# MCU.net
KiCad netlist of a schematic drawn in Altium Designer
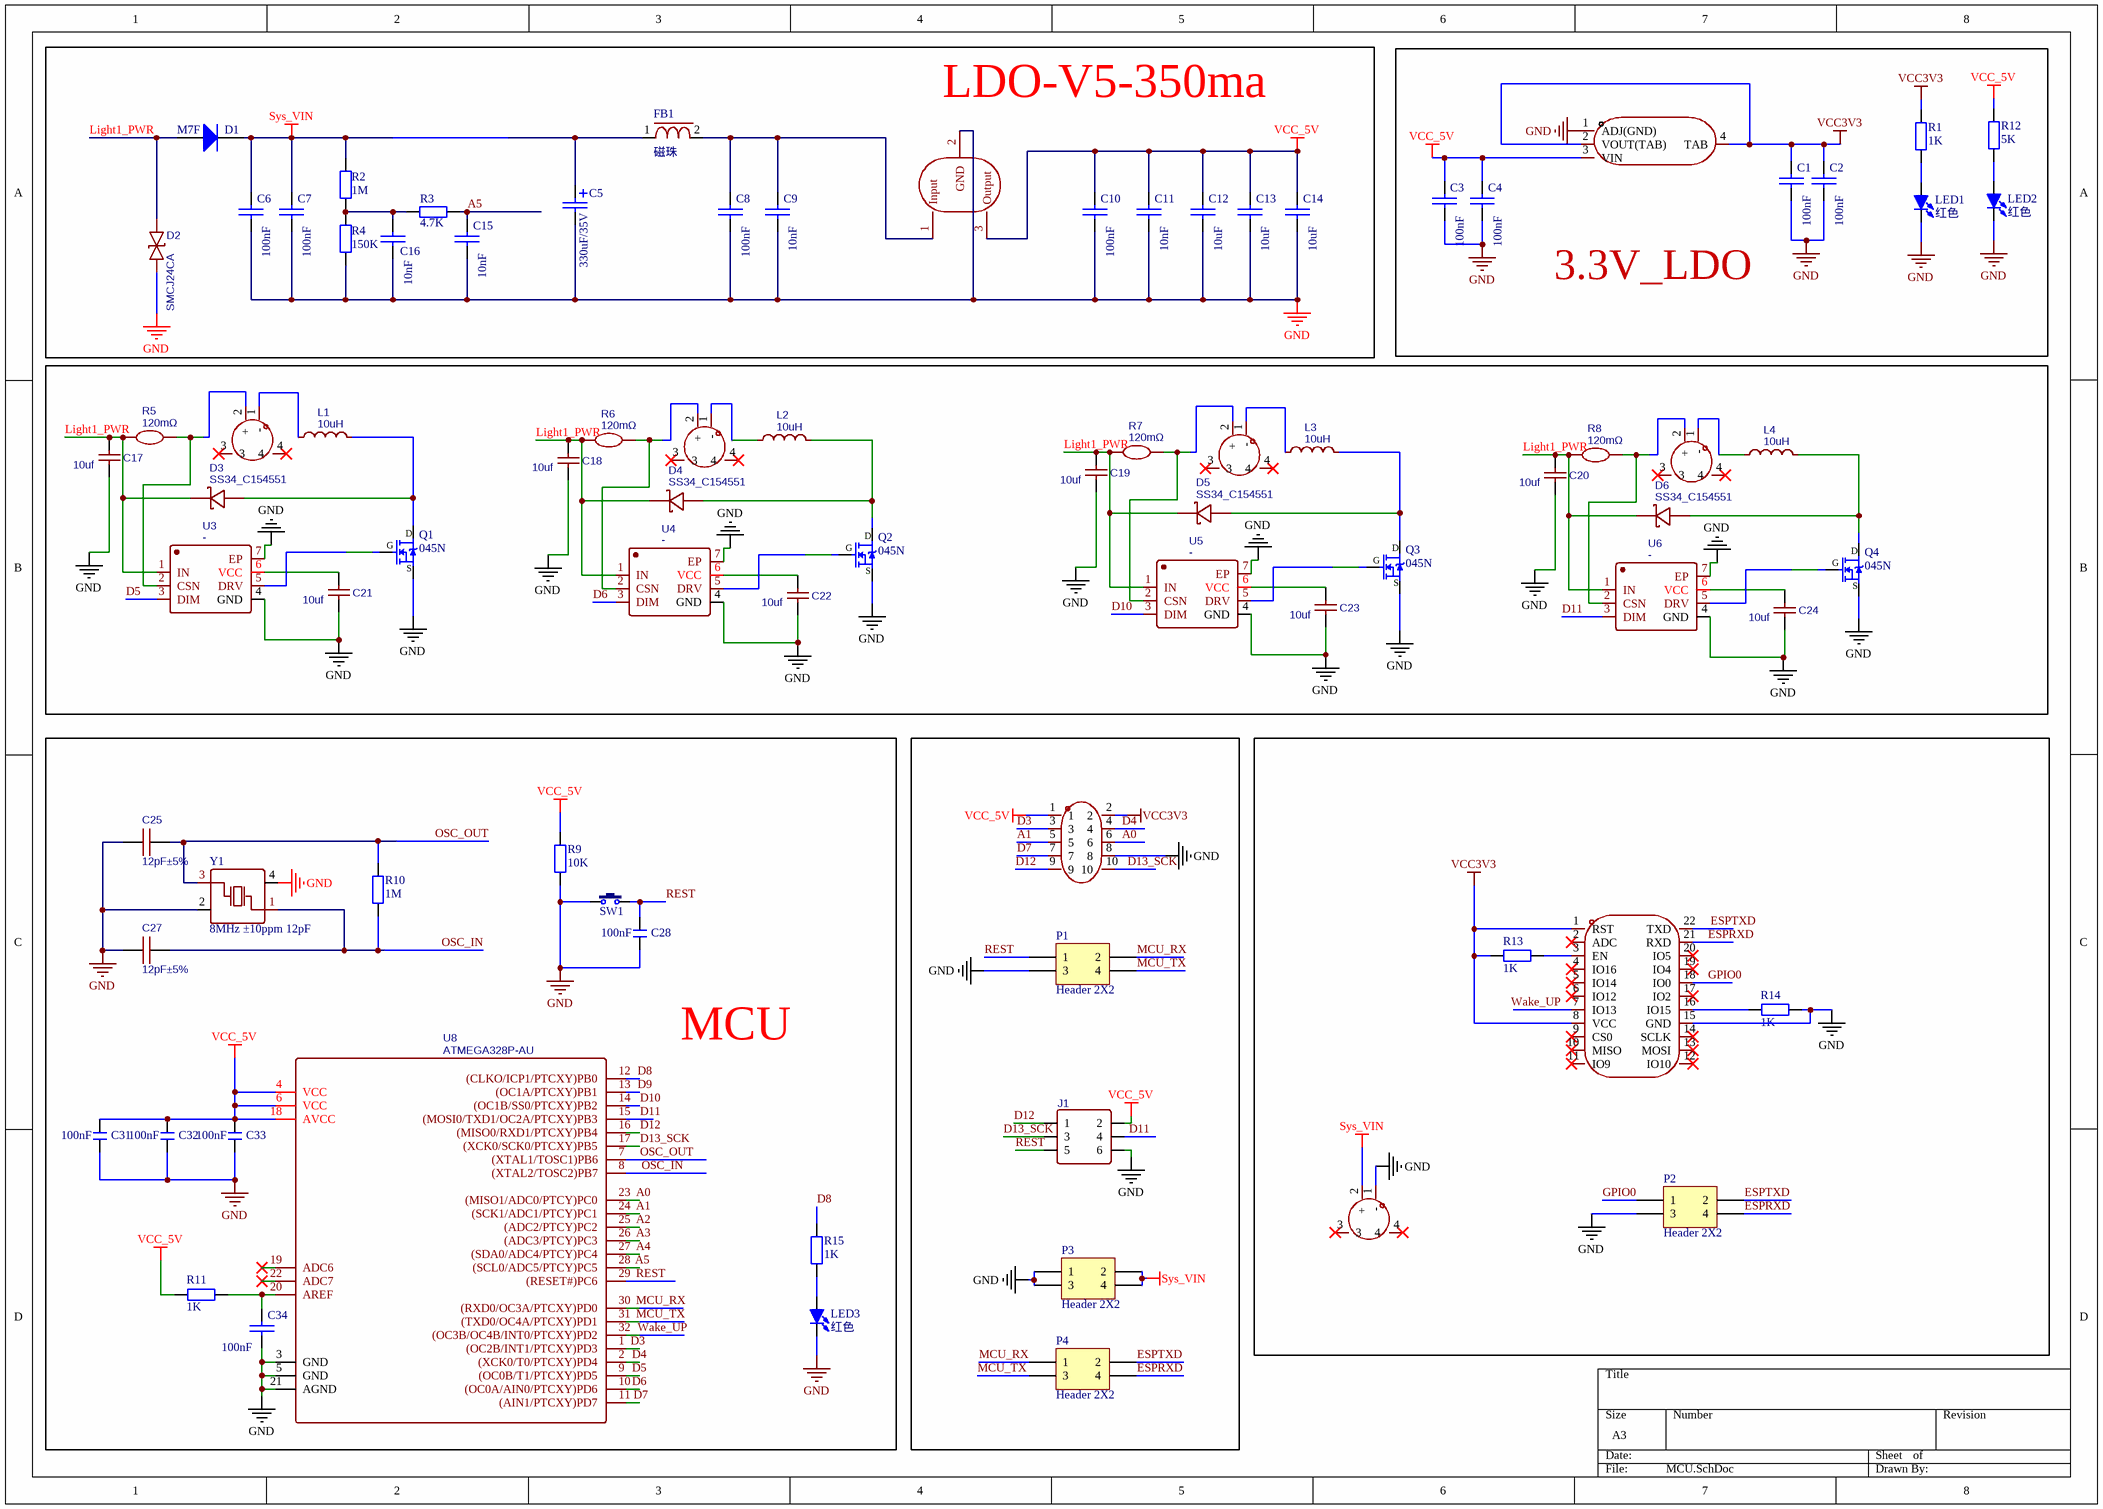
[diagram p0: MCU.SchDoc]

(export (version "E")
  (design (tool "Eeschema 10.0.6"))
  (components
    (comp (ref "C1")
      (value "100nF")
      (footprint "C_0603")
      (description "C_")
      (libsource (lib "MySchlib") (part "C_"))
    )
    (comp (ref "C2")
      (value "100nF")
      (footprint "C_0603")
      (description "C_")
      (libsource (lib "MySchlib") (part "C_"))
    )
    (comp (ref "C3")
      (value "100nF")
      (footprint "C_0603")
      (description "C_")
      (libsource (lib "MySchlib") (part "C_"))
    )
    (comp (ref "C4")
      (value "100nF")
      (footprint "C_0603")
      (description "C_")
      (libsource (lib "MySchlib") (part "C_"))
    )
    (comp (ref "C5")
      (value "330uF/35V")
      (footprint "9*H11MM")
      (description "RV331M035G105ETR，贴片电解，330u/35V/±20%/10X10.5")
      (libsource (lib "MySchlib") (part "C_ELEC_330uF,35V,10.0x10.5,CAPXON"))
    )
    (comp (ref "C6")
      (value "100nF")
      (footprint "C_0603")
      (description "C_")
      (libsource (lib "MySchlib") (part "C_"))
    )
    (comp (ref "C7")
      (value "100nF")
      (footprint "C_0603")
      (description "C_")
      (libsource (lib "MySchlib") (part "C_"))
    )
    (comp (ref "C8")
      (value "100nF")
      (footprint "C_0603")
      (description "C_")
      (libsource (lib "MySchlib") (part "C_"))
    )
    (comp (ref "C9")
      (value "10nF")
      (footprint "C_0603")
      (description "C_")
      (libsource (lib "MySchlib") (part "C_"))
    )
    (comp (ref "C10")
      (value "100nF")
      (footprint "C_0603")
      (description "C_")
      (libsource (lib "MySchlib") (part "C_"))
    )
    (comp (ref "C11")
      (value "10nF")
      (footprint "C_0603")
      (description "C_")
      (libsource (lib "MySchlib") (part "C_"))
    )
    (comp (ref "C12")
      (value "10uF")
      (footprint "C_1206")
      (description "C_")
      (libsource (lib "MySchlib") (part "C_"))
    )
    (comp (ref "C13")
      (value "10uF")
      (footprint "C_1206")
      (description "C_")
      (libsource (lib "MySchlib") (part "C_"))
    )
    (comp (ref "C14")
      (value "10uF")
      (footprint "C_1206")
      (description "C_")
      (libsource (lib "MySchlib") (part "C_"))
    )
    (comp (ref "C15")
      (value "10nF")
      (footprint "C_0603")
      (description "C_")
      (libsource (lib "MySchlib") (part "C_"))
    )
    (comp (ref "C16")
      (value "10nF")
      (footprint "C_0603")
      (description "C_")
      (libsource (lib "MySchlib") (part "C_"))
    )
    (comp (ref "C17")
      (value "10uf")
      (footprint "C_0603")
      (fields
        (field (name "MANUFACTURER") "muRata(村田)")
        (field (name "MANUFACTURER PART") "GCM188R70J225KE22D")
      )
      (libsource (lib "altium-import") (part "root_1_10uf_"))
    )
    (comp (ref "C18")
      (value "10uf")
      (footprint "C_0603")
      (fields
        (field (name "MANUFACTURER") "muRata(村田)")
        (field (name "MANUFACTURER PART") "GCM188R70J225KE22D")
      )
      (libsource (lib "altium-import") (part "root_1_10uf_"))
    )
    (comp (ref "C19")
      (value "10uf")
      (footprint "C_0603")
      (fields
        (field (name "MANUFACTURER") "muRata(村田)")
        (field (name "MANUFACTURER PART") "GCM188R70J225KE22D")
      )
      (libsource (lib "altium-import") (part "root_1_10uf_"))
    )
    (comp (ref "C20")
      (value "10uf")
      (footprint "C_0603")
      (fields
        (field (name "MANUFACTURER") "muRata(村田)")
        (field (name "MANUFACTURER PART") "GCM188R70J225KE22D")
      )
      (libsource (lib "altium-import") (part "root_1_10uf_"))
    )
    (comp (ref "C21")
      (value "10uf")
      (footprint "C_0603")
      (fields
        (field (name "MANUFACTURER") "muRata(村田)")
        (field (name "MANUFACTURER PART") "GCM188R70J225KE22D")
      )
      (libsource (lib "altium-import") (part "root_1_10uf_"))
    )
    (comp (ref "C22")
      (value "10uf")
      (footprint "C_0603")
      (fields
        (field (name "MANUFACTURER") "muRata(村田)")
        (field (name "MANUFACTURER PART") "GCM188R70J225KE22D")
      )
      (libsource (lib "altium-import") (part "root_1_10uf_"))
    )
    (comp (ref "C23")
      (value "10uf")
      (footprint "C_0603")
      (fields
        (field (name "MANUFACTURER") "muRata(村田)")
        (field (name "MANUFACTURER PART") "GCM188R70J225KE22D")
      )
      (libsource (lib "altium-import") (part "root_1_10uf_"))
    )
    (comp (ref "C24")
      (value "10uf")
      (footprint "C_0603")
      (fields
        (field (name "MANUFACTURER") "muRata(村田)")
        (field (name "MANUFACTURER PART") "GCM188R70J225KE22D")
      )
      (libsource (lib "altium-import") (part "root_1_10uf_"))
    )
    (comp (ref "C25")
      (value "12pF±5%")
      (footprint "C_0603")
      (description "电容")
      (libsource (lib "项目常用") (part "CAP"))
    )
    (comp (ref "C27")
      (value "12pF±5%")
      (footprint "C_0603")
      (description "电容")
      (libsource (lib "项目常用") (part "CAP"))
    )
    (comp (ref "C28")
      (value "100nF")
      (footprint "C_0603")
      (description "无极性贴片电容")
      (fields (field (name "版权归属") "源创客"))
      (libsource (lib "BULETOOTH") (part "C"))
    )
    (comp (ref "C31")
      (value "100nF")
      (footprint "C_0603")
      (description "无极性贴片电容")
      (fields (field (name "版权归属") "源创客"))
      (libsource (lib "BULETOOTH") (part "C"))
    )
    (comp (ref "C32")
      (value "100nF")
      (footprint "C_0603")
      (description "无极性贴片电容")
      (fields (field (name "版权归属") "源创客"))
      (libsource (lib "BULETOOTH") (part "C"))
    )
    (comp (ref "C33")
      (value "100nF")
      (footprint "C_0603")
      (description "无极性贴片电容")
      (fields (field (name "版权归属") "源创客"))
      (libsource (lib "BULETOOTH") (part "C"))
    )
    (comp (ref "C34")
      (value "100nF")
      (footprint "C_0603")
      (description "C_")
      (libsource (lib "MySchlib") (part "C_"))
    )
    (comp (ref "CN1")
      (value "XT60PW-M")
      (footprint "CONN-TH_XT60PW-M - duplicate")
      (fields (field (name "MANUFACTURER") "AMASS(艾迈斯)"))
      (libsource (lib "altium-import") (part "root_3_XT60PW-M_"))
    )
    (comp (ref "CN2")
      (value "XT60PW-M")
      (footprint "CONN-TH_XT60PW-M - duplicate")
      (fields (field (name "MANUFACTURER") "AMASS(艾迈斯)"))
      (libsource (lib "altium-import") (part "root_3_XT60PW-M_"))
    )
    (comp (ref "CN3")
      (value "XT60PW-M")
      (footprint "CONN-TH_XT60PW-M - duplicate")
      (fields (field (name "MANUFACTURER") "AMASS(艾迈斯)"))
      (libsource (lib "altium-import") (part "root_3_XT60PW-M_"))
    )
    (comp (ref "CN4")
      (value "XT60PW-M")
      (footprint "CONN-TH_XT60PW-M - duplicate")
      (fields (field (name "MANUFACTURER") "AMASS(艾迈斯)"))
      (libsource (lib "altium-import") (part "root_3_XT60PW-M_"))
    )
    (comp (ref "CN5")
      (value "JL15EDGRHC-35005B02")
      (footprint "CONN-TH_5P-P3.50_JILN_JL15EDGRHC-35005B02")
      (fields (field (name "MANUFACTURER") "JILN(锦凌)"))
      (libsource (lib "altium-import") (part "root_0_JL15EDGRHC-35005B02_"))
    )
    (comp (ref "CN6")
      (value "XT60PW-M")
      (footprint "CONN-TH_XT60PW-M - duplicate")
      (fields (field (name "MANUFACTURER") "AMASS(艾迈斯)"))
      (libsource (lib "altium-import") (part "root_3_XT60PW-M_"))
    )
    (comp (ref "D1")
      (value "M7F")
      (footprint "SMA")
      (description "M7F,二极管/1000V/1A/1.1V/SMAF/-55oC~150oC")
      (libsource (lib "MySchlib") (part "D_M7F,SMAF,MCC"))
    )
    (comp (ref "D2")
      (value "SMCJ24CA")
      (footprint "SMC")
      (fields
        (field (name "BOM_SUPPLIER PART") "C169449")
        (field (name "BOM_MANUFACTURER PART") "SMBJ15CA")
        (field (name "CONTRIBUTOR") "LCSC")
      )
      (libsource (lib "项目常用") (part "SMBJ15CA"))
    )
    (comp (ref "D3")
      (value "SS34_C154551")
      (footprint "SMC")
      (fields
        (field (name "MANUFACTURER") "onsemi(安森美)")
        (field (name "MANUFACTURER PART") "SS34")
        (field (name "CONTRIBUTOR") "LCSC")
      )
      (libsource (lib "altium-import") (part "root_0_SS34_C154551_"))
    )
    (comp (ref "D4")
      (value "SS34_C154551")
      (footprint "SMC")
      (fields
        (field (name "MANUFACTURER") "onsemi(安森美)")
        (field (name "MANUFACTURER PART") "SS34")
        (field (name "CONTRIBUTOR") "LCSC")
      )
      (libsource (lib "altium-import") (part "root_0_SS34_C154551_"))
    )
    (comp (ref "D5")
      (value "SS34_C154551")
      (footprint "SMC")
      (fields
        (field (name "MANUFACTURER") "onsemi(安森美)")
        (field (name "MANUFACTURER PART") "SS34")
        (field (name "CONTRIBUTOR") "LCSC")
      )
      (libsource (lib "altium-import") (part "root_0_SS34_C154551_"))
    )
    (comp (ref "D6")
      (value "SS34_C154551")
      (footprint "SMC")
      (fields
        (field (name "MANUFACTURER") "onsemi(安森美)")
        (field (name "MANUFACTURER PART") "SS34")
        (field (name "CONTRIBUTOR") "LCSC")
      )
      (libsource (lib "altium-import") (part "root_0_SS34_C154551_"))
    )
    (comp (ref "FB1")
      (value "磁珠")
      (footprint "R_0805")
      (description "UPB201209T-101Y-N,磁珠/100Ω/5A/0805,奇力新")
      (libsource (lib "项目常用") (part "磁珠"))
    )
    (comp (ref "J1")
      (value "HDR-M-2.54_2x3")
      (footprint "HDR-3X2")
      (fields (field (name "BOM_SUPPLIER PART") "C65114") (field (name "CONTRIBUTOR") "LCEDA_Lib"))
      (libsource (lib "altium-import") (part "root_0_HDR-M-2.54_2x3_"))
    )
    (comp (ref "L1")
      (value "10uH")
      (footprint "IND-SMD_L7.0-W6.6_FXL0650")
      (fields
        (field (name "MANUFACTURER") "cjiang(长江微电)")
        (field (name "MANUFACTURER PART") "FXL0650-8R2-M")
        (field (name "CONTRIBUTOR") "LCSC")
      )
      (libsource (lib "altium-import") (part "root_0_10uH_"))
    )
    (comp (ref "L2")
      (value "10uH")
      (footprint "IND-SMD_L7.0-W6.6_FXL0650")
      (fields
        (field (name "MANUFACTURER") "cjiang(长江微电)")
        (field (name "MANUFACTURER PART") "FXL0650-8R2-M")
        (field (name "CONTRIBUTOR") "LCSC")
      )
      (libsource (lib "altium-import") (part "root_0_10uH_"))
    )
    (comp (ref "L3")
      (value "10uH")
      (footprint "IND-SMD_L7.0-W6.6_FXL0650")
      (fields
        (field (name "MANUFACTURER") "cjiang(长江微电)")
        (field (name "MANUFACTURER PART") "FXL0650-8R2-M")
        (field (name "CONTRIBUTOR") "LCSC")
      )
      (libsource (lib "altium-import") (part "root_0_10uH_"))
    )
    (comp (ref "L4")
      (value "10uH")
      (footprint "IND-SMD_L7.0-W6.6_FXL0650")
      (fields
        (field (name "MANUFACTURER") "cjiang(长江微电)")
        (field (name "MANUFACTURER PART") "FXL0650-8R2-M")
        (field (name "CONTRIBUTOR") "LCSC")
      )
      (libsource (lib "altium-import") (part "root_0_10uH_"))
    )
    (comp (ref "LED1")
      (value "红色")
      (footprint "LED 0805G")
      (description "贴片LED")
      (fields (field (name "版权归属") "源创客"))
      (libsource (lib "LED") (part "LED-SMD"))
    )
    (comp (ref "LED2")
      (value "红色")
      (footprint "LED 0805G")
      (description "贴片LED")
      (fields (field (name "版权归属") "源创客"))
      (libsource (lib "LED") (part "LED-SMD"))
    )
    (comp (ref "LED3")
      (value "红色")
      (footprint "LED 0805G")
      (description "贴片LED")
      (fields (field (name "版权归属") "源创客"))
      (libsource (lib "LED") (part "LED-SMD"))
    )
    (comp (ref "P1")
      (value "Header 2X2")
      (footprint "HDR-2X2")
      (description "Header, 2-Pin, Dual row")
      (fields (field (name "PUBLISHER") "Altium Limited"))
      (libsource (lib "Miscellaneous Connectors") (part "Header 2X2"))
    )
    (comp (ref "P2")
      (value "Header 2X2")
      (footprint "HDR-2X2")
      (description "Header, 2-Pin, Dual row")
      (fields (field (name "PUBLISHER") "Altium Limited"))
      (libsource (lib "Miscellaneous Connectors") (part "Header 2X2"))
    )
    (comp (ref "P3")
      (value "Header 2X2")
      (footprint "HDR-2X2")
      (description "Header, 2-Pin, Dual row")
      (fields (field (name "PUBLISHER") "Altium Limited"))
      (libsource (lib "Miscellaneous Connectors") (part "Header 2X2"))
    )
    (comp (ref "P4")
      (value "Header 2X2")
      (footprint "HDR-2X2")
      (description "Header, 2-Pin, Dual row")
      (fields (field (name "PUBLISHER") "Altium Limited"))
      (libsource (lib "Miscellaneous Connectors") (part "Header 2X2"))
    )
    (comp (ref "Q1")
      (value "045N")
      (footprint "TDSON-8_L5.9-W5.2-P1.27-BL")
      (description "CRSM045N04N2Z")
      (fields (field (name "版权归属") "源创客"))
      (libsource (lib "6.1   - 场效应管-可控硅") (part "10N65"))
    )
    (comp (ref "Q2")
      (value "045N")
      (footprint "TDSON-8_L5.9-W5.2-P1.27-BL")
      (description "CRSM045N04N2Z")
      (fields (field (name "版权归属") "源创客"))
      (libsource (lib "6.1   - 场效应管-可控硅") (part "10N65"))
    )
    (comp (ref "Q3")
      (value "045N")
      (footprint "TDSON-8_L5.9-W5.2-P1.27-BL")
      (description "CRSM045N04N2Z")
      (fields (field (name "版权归属") "源创客"))
      (libsource (lib "6.1   - 场效应管-可控硅") (part "10N65"))
    )
    (comp (ref "Q4")
      (value "045N")
      (footprint "TDSON-8_L5.9-W5.2-P1.27-BL")
      (description "CRSM045N04N2Z")
      (fields (field (name "版权归属") "源创客"))
      (libsource (lib "6.1   - 场效应管-可控硅") (part "10N65"))
    )
    (comp (ref "R1")
      (value "1K")
      (footprint "R_0603")
      (description "大功率电阻")
      (fields (field (name "版权归属") "源创客"))
      (libsource (lib "3.1   - 电阻-电容-电感") (part "RX"))
    )
    (comp (ref "R2")
      (value "1M")
      (footprint "R_0603")
      (description "贴片电阻")
      (libsource (lib "MySchlib") (part "R_"))
    )
    (comp (ref "R3")
      (value "4.7K")
      (footprint "R_0603")
      (description "贴片电阻")
      (libsource (lib "") (part "R__1"))
    )
    (comp (ref "R4")
      (value "150K")
      (footprint "R_0603")
      (description "贴片电阻")
      (libsource (lib "MySchlib") (part "R_"))
    )
    (comp (ref "R5")
      (value "120mΩ")
      (footprint "R 2512-HP")
      (fields
        (field (name "MANUFACTURER") "Milliohm(毫欧)")
        (field (name "MANUFACTURER PART") "HoJLR2512-3W-120mR-1%")
        (field (name "CONTRIBUTOR") "lcsc")
      )
      (libsource (lib "altium-import") (part "root_0_120mΩ_"))
    )
    (comp (ref "R6")
      (value "120mΩ")
      (footprint "R 2512-HP")
      (fields
        (field (name "MANUFACTURER") "Milliohm(毫欧)")
        (field (name "MANUFACTURER PART") "HoJLR2512-3W-120mR-1%")
        (field (name "CONTRIBUTOR") "lcsc")
      )
      (libsource (lib "altium-import") (part "root_0_120mΩ_"))
    )
    (comp (ref "R7")
      (value "120mΩ")
      (footprint "R 2512-HP")
      (fields
        (field (name "MANUFACTURER") "Milliohm(毫欧)")
        (field (name "MANUFACTURER PART") "HoJLR2512-3W-120mR-1%")
        (field (name "CONTRIBUTOR") "lcsc")
      )
      (libsource (lib "altium-import") (part "root_0_120mΩ_"))
    )
    (comp (ref "R8")
      (value "120mΩ")
      (footprint "R 2512-HP")
      (fields
        (field (name "MANUFACTURER") "Milliohm(毫欧)")
        (field (name "MANUFACTURER PART") "HoJLR2512-3W-120mR-1%")
        (field (name "CONTRIBUTOR") "lcsc")
      )
      (libsource (lib "altium-import") (part "root_0_120mΩ_"))
    )
    (comp (ref "R9")
      (value "10K")
      (footprint "R_0603")
      (description "大功率电阻")
      (fields (field (name "版权归属") "源创客"))
      (libsource (lib "3.1   - 电阻-电容-电感") (part "RX"))
    )
    (comp (ref "R10")
      (value "1M")
      (footprint "R_0603")
      (description "大功率电阻")
      (fields (field (name "版权归属") "源创客"))
      (libsource (lib "3.1   - 电阻-电容-电感") (part "RX"))
    )
    (comp (ref "R11")
      (value "1K")
      (footprint "R_0603")
      (description "大功率电阻")
      (fields (field (name "版权归属") "源创客"))
      (libsource (lib "3.1   - 电阻-电容-电感") (part "RX"))
    )
    (comp (ref "R12")
      (value "5K")
      (footprint "R_0603")
      (description "大功率电阻")
      (fields (field (name "版权归属") "源创客"))
      (libsource (lib "3.1   - 电阻-电容-电感") (part "RX"))
    )
    (comp (ref "R13")
      (value "1K")
      (footprint "R_0603")
      (description "大功率电阻")
      (fields (field (name "版权归属") "源创客"))
      (libsource (lib "3.1   - 电阻-电容-电感") (part "RX"))
    )
    (comp (ref "R14")
      (value "1K")
      (footprint "R_0603")
      (description "大功率电阻")
      (fields (field (name "版权归属") "源创客"))
      (libsource (lib "3.1   - 电阻-电容-电感") (part "RX"))
    )
    (comp (ref "R15")
      (value "1K")
      (footprint "R_0603")
      (description "大功率电阻")
      (fields (field (name "版权归属") "源创客"))
      (libsource (lib "3.1   - 电阻-电容-电感") (part "RX"))
    )
    (comp (ref "SW1")
      (value "3x6x5")
      (footprint "TSW SMD-3*6*2.5")
      (description "3x6轻触开关")
      (fields (field (name "版权归属") "源创客"))
      (libsource (lib "按键-开关") (part "TSW 3x6"))
    )
    (comp (ref "U1")
      (value "AMS1117-3.3")
      (footprint "SOT223_L")
      (fields (field (name "MANUFACTURER") "UMW(友台半导体)"))
      (libsource (lib "altium-import") (part "root_0_AMS1117-3.3_C347222_"))
    )
    (comp (ref "U2")
      (value "DIA7875B50TA3")
      (footprint "SOT223_N")
      (libsource (lib "MySchlib") (part "DIA7875"))
    )
    (comp (ref "U3")
      (value "-")
      (footprint "TDFN-6_L3.0-W3.0-P0.95-BL-EP")
      (fields
        (field (name "MANUFACTURER") "ADI(亚德诺)/MAXIM(美信)")
        (field (name "MANUFACTURER PART") "MAX16819ATT+T")
        (field (name "CONTRIBUTOR") "LCSC")
      )
      (libsource (lib "altium-import") (part "root_0_-_"))
    )
    (comp (ref "U4")
      (value "-")
      (footprint "TDFN-6_L3.0-W3.0-P0.95-BL-EP")
      (fields
        (field (name "MANUFACTURER") "ADI(亚德诺)/MAXIM(美信)")
        (field (name "MANUFACTURER PART") "MAX16819ATT+T")
        (field (name "CONTRIBUTOR") "LCSC")
      )
      (libsource (lib "altium-import") (part "root_0_-_"))
    )
    (comp (ref "U5")
      (value "-")
      (footprint "TDFN-6_L3.0-W3.0-P0.95-BL-EP")
      (fields
        (field (name "MANUFACTURER") "ADI(亚德诺)/MAXIM(美信)")
        (field (name "MANUFACTURER PART") "MAX16819ATT+T")
        (field (name "CONTRIBUTOR") "LCSC")
      )
      (libsource (lib "altium-import") (part "root_0_-_"))
    )
    (comp (ref "U6")
      (value "-")
      (footprint "TDFN-6_L3.0-W3.0-P0.95-BL-EP")
      (fields
        (field (name "MANUFACTURER") "ADI(亚德诺)/MAXIM(美信)")
        (field (name "MANUFACTURER PART") "MAX16819ATT+T")
        (field (name "CONTRIBUTOR") "LCSC")
      )
      (libsource (lib "altium-import") (part "root_0_-_"))
    )
    (comp (ref "U7")
      (value "2.4GHz")
      (footprint "WIRELM-SMD_ESP-12F")
      (fields (field (name "MANUFACTURER") "DOIT(四博智联)") (field (name "MANUFACTURER PART") "ESP-12F"))
      (libsource (lib "altium-import") (part "root_0_ESP-12F_"))
    )
    (comp (ref "U8")
      (value "ATMEGA328P-AU")
      (footprint "TQFP-32_L7.0-W7.0-P0.80-LS9.0-BL")
      (fields (field (name "BOM_SUPPLIER PART") "C14877") (field (name "CONTRIBUTOR") "13471635540"))
      (libsource (lib "altium-import") (part "root_0_ATMEGA328P-AU_"))
    )
    (comp (ref "Y1")
      (value "8MHz ±10ppm 12pF")
      (footprint "SMD-3225-4P")
      (libsource (lib "项目常用") (part "晶振4P"))
    )
  )
  (nets
    (net (code "1") (name "/A0") (class "Default")
      (node (ref "CN5") (pin "6") (pinfunction "6_6") (pintype "passive"))
      (node (ref "U8") (pin "23") (pinfunction "(MISO1/ADC0/PTCY)PC0_23") (pintype "passive"))
    )
    (net (code "2") (name "/A1") (class "Default")
      (node (ref "CN5") (pin "5") (pinfunction "5_5") (pintype "passive"))
      (node (ref "U8") (pin "24") (pinfunction "(SCK1/ADC1/PTCY)PC1_24") (pintype "passive"))
    )
    (net (code "3") (name "/A2") (class "Default")
      (node (ref "U8") (pin "25") (pinfunction "(ADC2/PTCY)PC2_25") (pintype "passive"))
    )
    (net (code "4") (name "/A3") (class "Default")
      (node (ref "U8") (pin "26") (pinfunction "(ADC3/PTCY)PC3_26") (pintype "passive"))
    )
    (net (code "5") (name "/A4") (class "Default")
      (node (ref "U8") (pin "27") (pinfunction "(SDA0/ADC4/PTCY)PC4_27") (pintype "passive"))
    )
    (net (code "6") (name "/A5") (class "Default")
      (node (ref "C15") (pin "1") (pinfunction "1_1") (pintype "passive"))
      (node (ref "R3") (pin "1") (pinfunction "1_1") (pintype "passive"))
      (node (ref "U8") (pin "28") (pinfunction "(SCL0/ADC5/PTCY)PC5_28") (pintype "passive"))
    )
    (net (code "7") (name "/D3") (class "Default")
      (node (ref "CN5") (pin "3") (pinfunction "3_3") (pintype "passive"))
      (node (ref "U8") (pin "1") (pinfunction "(OC2B/INT1/PTCXY)PD3_1") (pintype "passive"))
    )
    (net (code "8") (name "/D4") (class "Default")
      (node (ref "CN5") (pin "4") (pinfunction "4_4") (pintype "passive"))
      (node (ref "U8") (pin "2") (pinfunction "(XCK0/T0/PTCXY)PD4_2") (pintype "passive"))
    )
    (net (code "9") (name "/D5") (class "Default")
      (node (ref "U3") (pin "3") (pinfunction "DIM_3") (pintype "passive"))
      (node (ref "U8") (pin "9") (pinfunction "(OC0B/T1/PTCXY)PD5_9") (pintype "passive"))
    )
    (net (code "10") (name "/D6") (class "Default")
      (node (ref "U4") (pin "3") (pinfunction "DIM_3") (pintype "passive"))
      (node (ref "U8") (pin "10") (pinfunction "(OC0A/AIN0/PTCXY)PD6_10") (pintype "passive"))
    )
    (net (code "11") (name "/D7") (class "Default")
      (node (ref "CN5") (pin "7") (pinfunction "7_7") (pintype "passive"))
      (node (ref "U8") (pin "11") (pinfunction "(AIN1/PTCXY)PD7_11") (pintype "passive"))
    )
    (net (code "12") (name "/D8") (class "Default")
      (node (ref "R15") (pin "2") (pinfunction "2_2") (pintype "passive"))
      (node (ref "U8") (pin "12") (pinfunction "(CLKO/ICP1/PTCXY)PB0_12") (pintype "passive"))
    )
    (net (code "13") (name "/D9") (class "Default")
      (node (ref "U8") (pin "13") (pinfunction "(OC1A/PTCXY)PB1_13") (pintype "passive"))
    )
    (net (code "14") (name "/D10") (class "Default")
      (node (ref "U5") (pin "3") (pinfunction "DIM_3") (pintype "passive"))
      (node (ref "U8") (pin "14") (pinfunction "(OC1B/SS0/PTCXY)PB2_14") (pintype "passive"))
    )
    (net (code "15") (name "/D11") (class "Default")
      (node (ref "J1") (pin "4") (pinfunction "4_4") (pintype "passive"))
      (node (ref "U6") (pin "3") (pinfunction "DIM_3") (pintype "passive"))
      (node (ref "U8") (pin "15") (pinfunction "(MOSI0/TXD1/OC2A/PTCXY)PB3_15") (pintype "passive"))
    )
    (net (code "16") (name "/D12") (class "Default")
      (node (ref "CN5") (pin "9") (pinfunction "9_9") (pintype "passive"))
      (node (ref "J1") (pin "1") (pinfunction "1_1") (pintype "passive"))
      (node (ref "U8") (pin "16") (pinfunction "(MISO0/RXD1/PTCXY)PB4_16") (pintype "passive"))
    )
    (net (code "17") (name "/D13_SCK") (class "Default")
      (node (ref "CN5") (pin "10") (pinfunction "10_10") (pintype "passive"))
      (node (ref "J1") (pin "3") (pinfunction "3_3") (pintype "passive"))
      (node (ref "U8") (pin "17") (pinfunction "(XCK0/SCK0/PTCXY)PB5_17") (pintype "passive"))
    )
    (net (code "18") (name "/ESPRXD") (class "Default")
      (node (ref "P2") (pin "4") (pinfunction "4_4") (pintype "passive"))
      (node (ref "P4") (pin "4") (pinfunction "4_4") (pintype "passive"))
      (node (ref "U7") (pin "21") (pinfunction "RXD_21") (pintype "passive"))
    )
    (net (code "19") (name "/ESPTXD") (class "Default")
      (node (ref "P2") (pin "2") (pinfunction "2_2") (pintype "passive"))
      (node (ref "P4") (pin "2") (pinfunction "2_2") (pintype "passive"))
      (node (ref "U7") (pin "22") (pinfunction "TXD_22") (pintype "passive"))
    )
    (net (code "20") (name "/GPIO0") (class "Default")
      (node (ref "P2") (pin "1") (pinfunction "1_1") (pintype "passive"))
      (node (ref "U7") (pin "18") (pinfunction "IO0_18") (pintype "passive"))
    )
    (net (code "21") (name "/Light1_PWR") (class "Default")
      (node (ref "C17") (pin "2") (pinfunction "2_2") (pintype "passive"))
      (node (ref "C18") (pin "2") (pinfunction "2_2") (pintype "passive"))
      (node (ref "C19") (pin "2") (pinfunction "2_2") (pintype "passive"))
      (node (ref "C20") (pin "2") (pinfunction "2_2") (pintype "passive"))
      (node (ref "D1") (pin "1") (pinfunction "A_1") (pintype "passive"))
      (node (ref "D2") (pin "1") (pinfunction "1_1") (pintype "passive"))
      (node (ref "D3") (pin "1") (pinfunction "C_1") (pintype "passive"))
      (node (ref "D4") (pin "1") (pinfunction "C_1") (pintype "passive"))
      (node (ref "D5") (pin "1") (pinfunction "C_1") (pintype "passive"))
      (node (ref "D6") (pin "1") (pinfunction "C_1") (pintype "passive"))
      (node (ref "R5") (pin "1") (pinfunction "1_1") (pintype "passive"))
      (node (ref "R6") (pin "1") (pinfunction "1_1") (pintype "passive"))
      (node (ref "R7") (pin "1") (pinfunction "1_1") (pintype "passive"))
      (node (ref "R8") (pin "1") (pinfunction "1_1") (pintype "passive"))
      (node (ref "U3") (pin "1") (pinfunction "IN_1") (pintype "passive"))
      (node (ref "U4") (pin "1") (pinfunction "IN_1") (pintype "passive"))
      (node (ref "U5") (pin "1") (pinfunction "IN_1") (pintype "passive"))
      (node (ref "U6") (pin "1") (pinfunction "IN_1") (pintype "passive"))
    )
    (net (code "22") (name "/MCU_RX") (class "Default")
      (node (ref "P1") (pin "2") (pinfunction "2_2") (pintype "passive"))
      (node (ref "P4") (pin "1") (pinfunction "1_1") (pintype "passive"))
      (node (ref "U8") (pin "30") (pinfunction "(RXD0/OC3A/PTCXY)PD0_30") (pintype "passive"))
    )
    (net (code "23") (name "/MCU_TX") (class "Default")
      (node (ref "P1") (pin "4") (pinfunction "4_4") (pintype "passive"))
      (node (ref "P4") (pin "3") (pinfunction "3_3") (pintype "passive"))
      (node (ref "U8") (pin "31") (pinfunction "(TXD0/OC4A/PTCXY)PD1_31") (pintype "passive"))
    )
    (net (code "24") (name "/OSC_IN") (class "Default")
      (node (ref "C27") (pin "2") (pinfunction "K_2") (pintype "passive"))
      (node (ref "R10") (pin "1") (pinfunction "1_1") (pintype "passive"))
      (node (ref "U8") (pin "8") (pinfunction "(XTAL2/TOSC2)PB7_8") (pintype "passive"))
      (node (ref "Y1") (pin "1") (pinfunction "OSC1_1") (pintype "passive"))
    )
    (net (code "25") (name "/OSC_OUT") (class "Default")
      (node (ref "C25") (pin "2") (pinfunction "K_2") (pintype "passive"))
      (node (ref "R10") (pin "2") (pinfunction "2_2") (pintype "passive"))
      (node (ref "U8") (pin "7") (pinfunction "(XTAL1/TOSC1)PB6_7") (pintype "passive"))
      (node (ref "Y1") (pin "3") (pinfunction "OSC2_3") (pintype "passive"))
    )
    (net (code "26") (name "/REST") (class "Default")
      (node (ref "C28") (pin "2") (pinfunction "2_2") (pintype "passive"))
      (node (ref "J1") (pin "5") (pinfunction "5_5") (pintype "passive"))
      (node (ref "P1") (pin "1") (pinfunction "1_1") (pintype "passive"))
      (node (ref "SW1") (pin "2") (pinfunction "2_2") (pintype "passive"))
      (node (ref "U8") (pin "29") (pinfunction "(RESET#)PC6_29") (pintype "passive"))
    )
    (net (code "27") (name "/Wake_UP") (class "Default")
      (node (ref "U8") (pin "32") (pinfunction "(OC3B/OC4B/INT0/PTCXY)PD2_32") (pintype "passive"))
    )
    (net (code "28") (name "GND") (class "Default")
      (node (ref "C1") (pin "2") (pinfunction "2_2") (pintype "passive"))
      (node (ref "C10") (pin "2") (pinfunction "2_2") (pintype "passive"))
      (node (ref "C11") (pin "2") (pinfunction "2_2") (pintype "passive"))
      (node (ref "C12") (pin "2") (pinfunction "2_2") (pintype "passive"))
      (node (ref "C13") (pin "2") (pinfunction "2_2") (pintype "passive"))
      (node (ref "C14") (pin "2") (pinfunction "2_2") (pintype "passive"))
      (node (ref "C15") (pin "2") (pinfunction "2_2") (pintype "passive"))
      (node (ref "C16") (pin "2") (pinfunction "2_2") (pintype "passive"))
      (node (ref "C17") (pin "1") (pinfunction "1_1") (pintype "passive"))
      (node (ref "C18") (pin "1") (pinfunction "1_1") (pintype "passive"))
      (node (ref "C19") (pin "1") (pinfunction "1_1") (pintype "passive"))
      (node (ref "C2") (pin "2") (pinfunction "2_2") (pintype "passive"))
      (node (ref "C20") (pin "1") (pinfunction "1_1") (pintype "passive"))
      (node (ref "C21") (pin "1") (pinfunction "1_1") (pintype "passive"))
      (node (ref "C22") (pin "1") (pinfunction "1_1") (pintype "passive"))
      (node (ref "C23") (pin "1") (pinfunction "1_1") (pintype "passive"))
      (node (ref "C24") (pin "1") (pinfunction "1_1") (pintype "passive"))
      (node (ref "C25") (pin "1") (pinfunction "A_1") (pintype "passive"))
      (node (ref "C27") (pin "1") (pinfunction "A_1") (pintype "passive"))
      (node (ref "C28") (pin "1") (pinfunction "1_1") (pintype "passive"))
      (node (ref "C3") (pin "2") (pinfunction "2_2") (pintype "passive"))
      (node (ref "C31") (pin "1") (pinfunction "1_1") (pintype "passive"))
      (node (ref "C32") (pin "1") (pinfunction "1_1") (pintype "passive"))
      (node (ref "C33") (pin "1") (pinfunction "1_1") (pintype "passive"))
      (node (ref "C34") (pin "2") (pinfunction "2_2") (pintype "passive"))
      (node (ref "C4") (pin "2") (pinfunction "2_2") (pintype "passive"))
      (node (ref "C5") (pin "2") (pinfunction "2_2") (pintype "passive"))
      (node (ref "C6") (pin "2") (pinfunction "2_2") (pintype "passive"))
      (node (ref "C7") (pin "2") (pinfunction "2_2") (pintype "passive"))
      (node (ref "C8") (pin "2") (pinfunction "2_2") (pintype "passive"))
      (node (ref "C9") (pin "2") (pinfunction "2_2") (pintype "passive"))
      (node (ref "CN5") (pin "8") (pinfunction "8_8") (pintype "passive"))
      (node (ref "CN6") (pin "1") (pinfunction "-_1") (pintype "passive"))
      (node (ref "D2") (pin "2") (pinfunction "2_2") (pintype "passive"))
      (node (ref "J1") (pin "6") (pinfunction "6_6") (pintype "passive"))
      (node (ref "LED1") (pin "2") (pinfunction "K_2") (pintype "passive"))
      (node (ref "LED2") (pin "2") (pinfunction "K_2") (pintype "passive"))
      (node (ref "LED3") (pin "2") (pinfunction "K_2") (pintype "passive"))
      (node (ref "P1") (pin "3") (pinfunction "3_3") (pintype "passive"))
      (node (ref "P2") (pin "3") (pinfunction "3_3") (pintype "passive"))
      (node (ref "P3") (pin "1") (pinfunction "1_1") (pintype "passive"))
      (node (ref "P3") (pin "3") (pinfunction "3_3") (pintype "passive"))
      (node (ref "Q1") (pin "3") (pinfunction "D_3") (pintype "passive"))
      (node (ref "Q2") (pin "3") (pinfunction "D_3") (pintype "passive"))
      (node (ref "Q3") (pin "3") (pinfunction "D_3") (pintype "passive"))
      (node (ref "Q4") (pin "3") (pinfunction "D_3") (pintype "passive"))
      (node (ref "R14") (pin "1") (pinfunction "1_1") (pintype "passive"))
      (node (ref "R4") (pin "1") (pinfunction "1_1") (pintype "passive"))
      (node (ref "R9") (pin "1") (pinfunction "1_1") (pintype "passive"))
      (node (ref "SW1") (pin "1") (pinfunction "1_1") (pintype "passive"))
      (node (ref "U1") (pin "1") (pinfunction "ADJ(GND)_1") (pintype "passive"))
      (node (ref "U2") (pin "2") (pinfunction "GND_2") (pintype "passive"))
      (node (ref "U3") (pin "4") (pinfunction "GND_4") (pintype "passive"))
      (node (ref "U3") (pin "7") (pinfunction "EP_7") (pintype "passive"))
      (node (ref "U4") (pin "4") (pinfunction "GND_4") (pintype "passive"))
      (node (ref "U4") (pin "7") (pinfunction "EP_7") (pintype "passive"))
      (node (ref "U5") (pin "4") (pinfunction "GND_4") (pintype "passive"))
      (node (ref "U5") (pin "7") (pinfunction "EP_7") (pintype "passive"))
      (node (ref "U6") (pin "4") (pinfunction "GND_4") (pintype "passive"))
      (node (ref "U6") (pin "7") (pinfunction "EP_7") (pintype "passive"))
      (node (ref "U7") (pin "15") (pinfunction "GND_15") (pintype "passive"))
      (node (ref "U8") (pin "21") (pinfunction "AGND_21") (pintype "passive"))
      (node (ref "U8") (pin "3") (pinfunction "GND_3") (pintype "passive"))
      (node (ref "U8") (pin "5") (pinfunction "GND_5") (pintype "passive"))
      (node (ref "Y1") (pin "2") (pinfunction "GND_2") (pintype "passive"))
      (node (ref "Y1") (pin "4") (pinfunction "GND_4") (pintype "passive"))
    )
    (net (code "29") (name "Net-(C16-Pad1)") (class "Default")
      (node (ref "C16") (pin "1") (pinfunction "1_1") (pintype "passive"))
      (node (ref "R2") (pin "1") (pinfunction "1_1") (pintype "passive"))
      (node (ref "R3") (pin "2") (pinfunction "2_2") (pintype "passive"))
      (node (ref "R4") (pin "2") (pinfunction "2_2") (pintype "passive"))
    )
    (net (code "30") (name "Net-(CN1-+)") (class "Default")
      (node (ref "CN1") (pin "2") (pinfunction "+_2") (pintype "passive"))
      (node (ref "R5") (pin "2") (pinfunction "2_2") (pintype "passive"))
      (node (ref "U3") (pin "2") (pinfunction "CSN_2") (pintype "passive"))
    )
    (net (code "31") (name "Net-(CN1--)") (class "Default")
      (node (ref "CN1") (pin "1") (pinfunction "-_1") (pintype "passive"))
      (node (ref "L1") (pin "1") (pinfunction "1_1") (pintype "passive"))
    )
    (net (code "32") (name "Net-(CN2-+)") (class "Default")
      (node (ref "CN2") (pin "2") (pinfunction "+_2") (pintype "passive"))
      (node (ref "R6") (pin "2") (pinfunction "2_2") (pintype "passive"))
      (node (ref "U4") (pin "2") (pinfunction "CSN_2") (pintype "passive"))
    )
    (net (code "33") (name "Net-(CN2--)") (class "Default")
      (node (ref "CN2") (pin "1") (pinfunction "-_1") (pintype "passive"))
      (node (ref "L2") (pin "1") (pinfunction "1_1") (pintype "passive"))
    )
    (net (code "34") (name "Net-(CN3-+)") (class "Default")
      (node (ref "CN3") (pin "2") (pinfunction "+_2") (pintype "passive"))
      (node (ref "R7") (pin "2") (pinfunction "2_2") (pintype "passive"))
      (node (ref "U5") (pin "2") (pinfunction "CSN_2") (pintype "passive"))
    )
    (net (code "35") (name "Net-(CN3--)") (class "Default")
      (node (ref "CN3") (pin "1") (pinfunction "-_1") (pintype "passive"))
      (node (ref "L3") (pin "1") (pinfunction "1_1") (pintype "passive"))
    )
    (net (code "36") (name "Net-(CN4-+)") (class "Default")
      (node (ref "CN4") (pin "2") (pinfunction "+_2") (pintype "passive"))
      (node (ref "R8") (pin "2") (pinfunction "2_2") (pintype "passive"))
      (node (ref "U6") (pin "2") (pinfunction "CSN_2") (pintype "passive"))
    )
    (net (code "37") (name "Net-(CN4--)") (class "Default")
      (node (ref "CN4") (pin "1") (pinfunction "-_1") (pintype "passive"))
      (node (ref "L4") (pin "1") (pinfunction "1_1") (pintype "passive"))
    )
    (net (code "38") (name "Net-(D3-A)") (class "Default")
      (node (ref "D3") (pin "2") (pinfunction "A_2") (pintype "passive"))
      (node (ref "L1") (pin "2") (pinfunction "2_2") (pintype "passive"))
      (node (ref "Q1") (pin "2") (pinfunction "S_2") (pintype "passive"))
    )
    (net (code "39") (name "Net-(D4-A)") (class "Default")
      (node (ref "D4") (pin "2") (pinfunction "A_2") (pintype "passive"))
      (node (ref "L2") (pin "2") (pinfunction "2_2") (pintype "passive"))
      (node (ref "Q2") (pin "2") (pinfunction "S_2") (pintype "passive"))
    )
    (net (code "40") (name "Net-(D5-A)") (class "Default")
      (node (ref "D5") (pin "2") (pinfunction "A_2") (pintype "passive"))
      (node (ref "L3") (pin "2") (pinfunction "2_2") (pintype "passive"))
      (node (ref "Q3") (pin "2") (pinfunction "S_2") (pintype "passive"))
    )
    (net (code "41") (name "Net-(D6-A)") (class "Default")
      (node (ref "D6") (pin "2") (pinfunction "A_2") (pintype "passive"))
      (node (ref "L4") (pin "2") (pinfunction "2_2") (pintype "passive"))
      (node (ref "Q4") (pin "2") (pinfunction "S_2") (pintype "passive"))
    )
    (net (code "42") (name "Net-(LED1-A)") (class "Default")
      (node (ref "LED1") (pin "1") (pinfunction "A_1") (pintype "passive"))
      (node (ref "R1") (pin "1") (pinfunction "1_1") (pintype "passive"))
    )
    (net (code "43") (name "Net-(LED2-A)") (class "Default")
      (node (ref "LED2") (pin "1") (pinfunction "A_1") (pintype "passive"))
      (node (ref "R12") (pin "1") (pinfunction "1_1") (pintype "passive"))
    )
    (net (code "44") (name "Net-(LED3-A)") (class "Default")
      (node (ref "LED3") (pin "1") (pinfunction "A_1") (pintype "passive"))
      (node (ref "R15") (pin "1") (pinfunction "1_1") (pintype "passive"))
    )
    (net (code "45") (name "Net-(Q1-G)") (class "Default")
      (node (ref "Q1") (pin "1") (pinfunction "G_1") (pintype "passive"))
      (node (ref "U3") (pin "5") (pinfunction "DRV_5") (pintype "passive"))
    )
    (net (code "46") (name "Net-(Q2-G)") (class "Default")
      (node (ref "Q2") (pin "1") (pinfunction "G_1") (pintype "passive"))
      (node (ref "U4") (pin "5") (pinfunction "DRV_5") (pintype "passive"))
    )
    (net (code "47") (name "Net-(Q3-G)") (class "Default")
      (node (ref "Q3") (pin "1") (pinfunction "G_1") (pintype "passive"))
      (node (ref "U5") (pin "5") (pinfunction "DRV_5") (pintype "passive"))
    )
    (net (code "48") (name "Net-(Q4-G)") (class "Default")
      (node (ref "Q4") (pin "1") (pinfunction "G_1") (pintype "passive"))
      (node (ref "U6") (pin "5") (pinfunction "DRV_5") (pintype "passive"))
    )
    (net (code "49") (name "Net-(U2-Input)") (class "Default")
      (node (ref "C8") (pin "1") (pinfunction "1_1") (pintype "passive"))
      (node (ref "C9") (pin "1") (pinfunction "1_1") (pintype "passive"))
      (node (ref "FB1") (pin "2") (pinfunction "2_2") (pintype "passive"))
      (node (ref "U2") (pin "1") (pinfunction "Input_1") (pintype "passive"))
    )
    (net (code "50") (name "Net-(U3-VCC)") (class "Default")
      (node (ref "C21") (pin "2") (pinfunction "2_2") (pintype "passive"))
      (node (ref "U3") (pin "6") (pinfunction "VCC_6") (pintype "passive"))
    )
    (net (code "51") (name "Net-(U4-VCC)") (class "Default")
      (node (ref "C22") (pin "2") (pinfunction "2_2") (pintype "passive"))
      (node (ref "U4") (pin "6") (pinfunction "VCC_6") (pintype "passive"))
    )
    (net (code "52") (name "Net-(U5-VCC)") (class "Default")
      (node (ref "C23") (pin "2") (pinfunction "2_2") (pintype "passive"))
      (node (ref "U5") (pin "6") (pinfunction "VCC_6") (pintype "passive"))
    )
    (net (code "53") (name "Net-(U6-VCC)") (class "Default")
      (node (ref "C24") (pin "2") (pinfunction "2_2") (pintype "passive"))
      (node (ref "U6") (pin "6") (pinfunction "VCC_6") (pintype "passive"))
    )
    (net (code "54") (name "Net-(U7-EN)") (class "Default")
      (node (ref "R13") (pin "1") (pinfunction "1_1") (pintype "passive"))
      (node (ref "U7") (pin "3") (pinfunction "EN_3") (pintype "passive"))
    )
    (net (code "55") (name "Net-(U7-IO15)") (class "Default")
      (node (ref "R14") (pin "2") (pinfunction "2_2") (pintype "passive"))
      (node (ref "U7") (pin "16") (pinfunction "IO15_16") (pintype "passive"))
    )
    (net (code "56") (name "Net-(U8-AREF)") (class "Default")
      (node (ref "C34") (pin "1") (pinfunction "1_1") (pintype "passive"))
      (node (ref "R11") (pin "1") (pinfunction "1_1") (pintype "passive"))
      (node (ref "U8") (pin "20") (pinfunction "AREF_20") (pintype "passive"))
    )
    (net (code "57") (name "Sys_VIN") (class "Default")
      (node (ref "C5") (pin "1") (pinfunction "1_1") (pintype "passive"))
      (node (ref "C6") (pin "1") (pinfunction "1_1") (pintype "passive"))
      (node (ref "C7") (pin "1") (pinfunction "1_1") (pintype "passive"))
      (node (ref "CN6") (pin "2") (pinfunction "+_2") (pintype "passive"))
      (node (ref "D1") (pin "2") (pinfunction "K_2") (pintype "passive"))
      (node (ref "FB1") (pin "1") (pinfunction "1_1") (pintype "passive"))
      (node (ref "P3") (pin "2") (pinfunction "2_2") (pintype "passive"))
      (node (ref "P3") (pin "4") (pinfunction "4_4") (pintype "passive"))
      (node (ref "R2") (pin "2") (pinfunction "2_2") (pintype "passive"))
    )
    (net (code "58") (name "VCC3V3") (class "Default")
      (node (ref "C1") (pin "1") (pinfunction "1_1") (pintype "passive"))
      (node (ref "C2") (pin "1") (pinfunction "1_1") (pintype "passive"))
      (node (ref "CN5") (pin "2") (pinfunction "2_2") (pintype "passive"))
      (node (ref "R1") (pin "2") (pinfunction "2_2") (pintype "passive"))
      (node (ref "R13") (pin "2") (pinfunction "2_2") (pintype "passive"))
      (node (ref "U1") (pin "2") (pinfunction "VOUT(TAB)_2") (pintype "passive"))
      (node (ref "U1") (pin "4") (pinfunction "TAB_4") (pintype "passive"))
      (node (ref "U7") (pin "1") (pinfunction "RST_1") (pintype "passive"))
      (node (ref "U7") (pin "8") (pinfunction "VCC_8") (pintype "passive"))
    )
    (net (code "59") (name "VCC_5V") (class "Default")
      (node (ref "C10") (pin "1") (pinfunction "1_1") (pintype "passive"))
      (node (ref "C11") (pin "1") (pinfunction "1_1") (pintype "passive"))
      (node (ref "C12") (pin "1") (pinfunction "1_1") (pintype "passive"))
      (node (ref "C13") (pin "1") (pinfunction "1_1") (pintype "passive"))
      (node (ref "C14") (pin "1") (pinfunction "1_1") (pintype "passive"))
      (node (ref "C3") (pin "1") (pinfunction "1_1") (pintype "passive"))
      (node (ref "C31") (pin "2") (pinfunction "2_2") (pintype "passive"))
      (node (ref "C32") (pin "2") (pinfunction "2_2") (pintype "passive"))
      (node (ref "C33") (pin "2") (pinfunction "2_2") (pintype "passive"))
      (node (ref "C4") (pin "1") (pinfunction "1_1") (pintype "passive"))
      (node (ref "CN5") (pin "1") (pinfunction "1_1") (pintype "passive"))
      (node (ref "J1") (pin "2") (pinfunction "2_2") (pintype "passive"))
      (node (ref "R11") (pin "2") (pinfunction "2_2") (pintype "passive"))
      (node (ref "R12") (pin "2") (pinfunction "2_2") (pintype "passive"))
      (node (ref "R9") (pin "2") (pinfunction "2_2") (pintype "passive"))
      (node (ref "U1") (pin "3") (pinfunction "VIN_3") (pintype "passive"))
      (node (ref "U2") (pin "3") (pinfunction "Output_3") (pintype "passive"))
      (node (ref "U8") (pin "18") (pinfunction "AVCC_18") (pintype "passive"))
      (node (ref "U8") (pin "4") (pinfunction "VCC_4") (pintype "passive"))
      (node (ref "U8") (pin "6") (pinfunction "VCC_6") (pintype "passive"))
    )
    (net (code "60") (name "unconnected-(CN1-Pad3)") (class "Default")
      (node (ref "CN1") (pin "3") (pinfunction "3_3") (pintype "passive+no_connect"))
    )
    (net (code "61") (name "unconnected-(CN1-Pad4)") (class "Default")
      (node (ref "CN1") (pin "4") (pinfunction "4_4") (pintype "passive+no_connect"))
    )
    (net (code "62") (name "unconnected-(CN2-Pad3)") (class "Default")
      (node (ref "CN2") (pin "3") (pinfunction "3_3") (pintype "passive+no_connect"))
    )
    (net (code "63") (name "unconnected-(CN2-Pad4)") (class "Default")
      (node (ref "CN2") (pin "4") (pinfunction "4_4") (pintype "passive+no_connect"))
    )
    (net (code "64") (name "unconnected-(CN3-Pad3)") (class "Default")
      (node (ref "CN3") (pin "3") (pinfunction "3_3") (pintype "passive+no_connect"))
    )
    (net (code "65") (name "unconnected-(CN3-Pad4)") (class "Default")
      (node (ref "CN3") (pin "4") (pinfunction "4_4") (pintype "passive+no_connect"))
    )
    (net (code "66") (name "unconnected-(CN4-Pad3)") (class "Default")
      (node (ref "CN4") (pin "3") (pinfunction "3_3") (pintype "passive+no_connect"))
    )
    (net (code "67") (name "unconnected-(CN4-Pad4)") (class "Default")
      (node (ref "CN4") (pin "4") (pinfunction "4_4") (pintype "passive+no_connect"))
    )
    (net (code "68") (name "unconnected-(CN6-Pad3)") (class "Default")
      (node (ref "CN6") (pin "3") (pinfunction "3_3") (pintype "passive+no_connect"))
    )
    (net (code "69") (name "unconnected-(CN6-Pad4)") (class "Default")
      (node (ref "CN6") (pin "4") (pinfunction "4_4") (pintype "passive+no_connect"))
    )
    (net (code "70") (name "unconnected-(U7-ADC-Pad2)") (class "Default")
      (node (ref "U7") (pin "2") (pinfunction "ADC_2") (pintype "passive+no_connect"))
    )
    (net (code "71") (name "unconnected-(U7-CS0-Pad9)") (class "Default")
      (node (ref "U7") (pin "9") (pinfunction "CS0_9") (pintype "passive+no_connect"))
    )
    (net (code "72") (name "unconnected-(U7-IO2-Pad17)") (class "Default")
      (node (ref "U7") (pin "17") (pinfunction "IO2_17") (pintype "passive+no_connect"))
    )
    (net (code "73") (name "unconnected-(U7-IO4-Pad19)") (class "Default")
      (node (ref "U7") (pin "19") (pinfunction "IO4_19") (pintype "passive+no_connect"))
    )
    (net (code "74") (name "unconnected-(U7-IO5-Pad20)") (class "Default")
      (node (ref "U7") (pin "20") (pinfunction "IO5_20") (pintype "passive+no_connect"))
    )
    (net (code "75") (name "unconnected-(U7-IO9-Pad11)") (class "Default")
      (node (ref "U7") (pin "11") (pinfunction "IO9_11") (pintype "passive+no_connect"))
    )
    (net (code "76") (name "unconnected-(U7-IO10-Pad12)") (class "Default")
      (node (ref "U7") (pin "12") (pinfunction "IO10_12") (pintype "passive+no_connect"))
    )
    (net (code "77") (name "unconnected-(U7-IO12-Pad6)") (class "Default")
      (node (ref "U7") (pin "6") (pinfunction "IO12_6") (pintype "passive+no_connect"))
    )
    (net (code "78") (name "unconnected-(U7-IO13-Pad7)") (class "Default")
      (node (ref "U7") (pin "7") (pinfunction "IO13_7") (pintype "passive"))
    )
    (net (code "79") (name "unconnected-(U7-IO14-Pad5)") (class "Default")
      (node (ref "U7") (pin "5") (pinfunction "IO14_5") (pintype "passive+no_connect"))
    )
    (net (code "80") (name "unconnected-(U7-IO16-Pad4)") (class "Default")
      (node (ref "U7") (pin "4") (pinfunction "IO16_4") (pintype "passive+no_connect"))
    )
    (net (code "81") (name "unconnected-(U7-MISO-Pad10)") (class "Default")
      (node (ref "U7") (pin "10") (pinfunction "MISO_10") (pintype "passive+no_connect"))
    )
    (net (code "82") (name "unconnected-(U7-MOSI-Pad13)") (class "Default")
      (node (ref "U7") (pin "13") (pinfunction "MOSI_13") (pintype "passive+no_connect"))
    )
    (net (code "83") (name "unconnected-(U7-SCLK-Pad14)") (class "Default")
      (node (ref "U7") (pin "14") (pinfunction "SCLK_14") (pintype "passive+no_connect"))
    )
    (net (code "84") (name "unconnected-(U8-ADC6-Pad19)") (class "Default")
      (node (ref "U8") (pin "19") (pinfunction "ADC6_19") (pintype "passive+no_connect"))
    )
    (net (code "85") (name "unconnected-(U8-ADC7-Pad22)") (class "Default")
      (node (ref "U8") (pin "22") (pinfunction "ADC7_22") (pintype "passive+no_connect"))
    )
  )
)
